# BG1094_RPi3b__Connector.net
KiCad netlist of a schematic drawn in Altium Designer
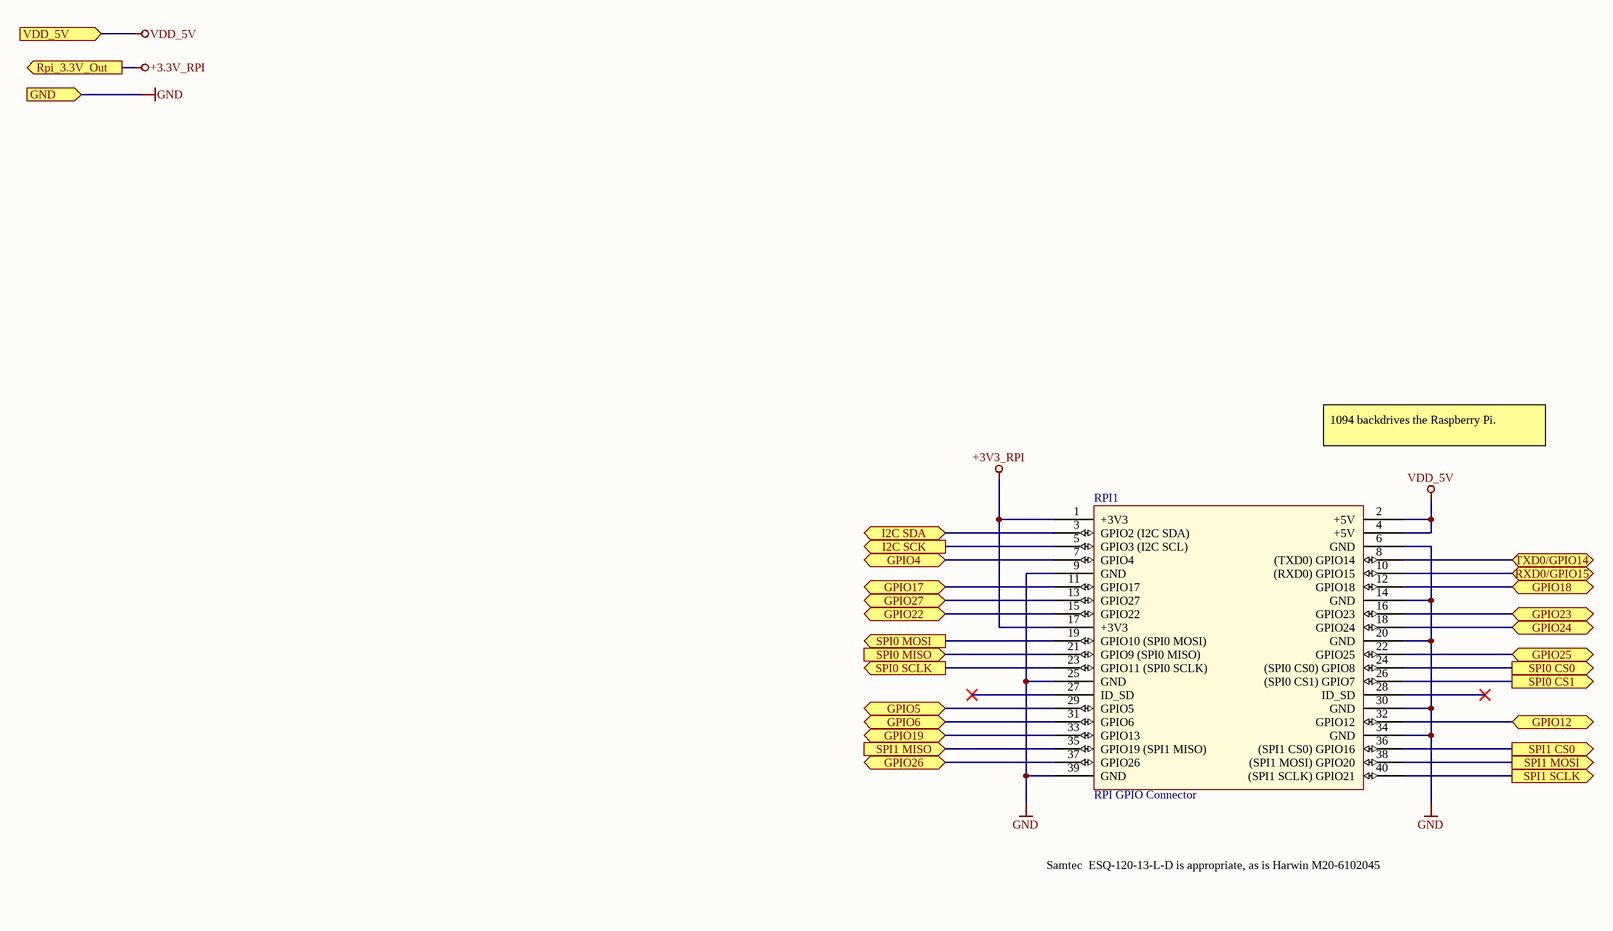
[diagram p0: BG1094_RPi3b+_Connector.SchDoc]

(export (version "E")
  (design (tool "Eeschema 10.0.6"))
  (components
    (comp (ref "RPI1")
      (value "RPI GPIO Connector")
      (footprint "Luxonis:rpi-hat-40-socket")
      (description "GPIO Header for Raspberry Pi A+/B+/Pi 2/Pi 3 - 2x20")
      (libsource (lib "Luxonis") (part "RPi HAT 40 Pin Connector"))
    )
  )
  (nets
    (net (code "2") (name "+3V3_RPI") (class "Default")
      (node (ref "RPI1") (pin "1") (pinfunction "+3V3_1") (pintype "power_in"))
      (node (ref "RPI1") (pin "17") (pinfunction "+3V3_17") (pintype "power_in"))
    )
    (net (code "3") (name "/GPIO4") (class "Default")
      (node (ref "RPI1") (pin "7") (pinfunction "GPIO4_7") (pintype "bidirectional"))
    )
    (net (code "4") (name "/GPIO5") (class "Default")
      (node (ref "RPI1") (pin "29") (pinfunction "GPIO5_29") (pintype "bidirectional"))
    )
    (net (code "5") (name "/GPIO6") (class "Default")
      (node (ref "RPI1") (pin "31") (pinfunction "GPIO6_31") (pintype "bidirectional"))
    )
    (net (code "6") (name "/GPIO12") (class "Default")
      (node (ref "RPI1") (pin "32") (pinfunction "GPIO12_32") (pintype "bidirectional"))
    )
    (net (code "7") (name "/GPIO17") (class "Default")
      (node (ref "RPI1") (pin "11") (pinfunction "GPIO17_11") (pintype "bidirectional"))
    )
    (net (code "8") (name "/GPIO18") (class "Default")
      (node (ref "RPI1") (pin "12") (pinfunction "GPIO18_12") (pintype "bidirectional"))
    )
    (net (code "9") (name "/GPIO19") (class "Default")
      (node (ref "RPI1") (pin "33") (pinfunction "GPIO13_33") (pintype "bidirectional"))
    )
    (net (code "10") (name "/GPIO22") (class "Default")
      (node (ref "RPI1") (pin "15") (pinfunction "GPIO22_15") (pintype "bidirectional"))
    )
    (net (code "11") (name "/GPIO23") (class "Default")
      (node (ref "RPI1") (pin "16") (pinfunction "GPIO23_16") (pintype "bidirectional"))
    )
    (net (code "12") (name "/GPIO24") (class "Default")
      (node (ref "RPI1") (pin "18") (pinfunction "GPIO24_18") (pintype "bidirectional"))
    )
    (net (code "13") (name "/GPIO25") (class "Default")
      (node (ref "RPI1") (pin "22") (pinfunction "GPIO25_22") (pintype "bidirectional"))
    )
    (net (code "14") (name "/GPIO26") (class "Default")
      (node (ref "RPI1") (pin "37") (pinfunction "GPIO26_37") (pintype "bidirectional"))
    )
    (net (code "15") (name "/GPIO27") (class "Default")
      (node (ref "RPI1") (pin "13") (pinfunction "GPIO27_13") (pintype "bidirectional"))
    )
    (net (code "16") (name "/I2C SCK") (class "Default")
      (node (ref "RPI1") (pin "5") (pinfunction "GPIO3_(I2C_SCL)_5") (pintype "bidirectional"))
    )
    (net (code "17") (name "/I2C SDA") (class "Default")
      (node (ref "RPI1") (pin "3") (pinfunction "GPIO2_(I2C_SDA)_3") (pintype "bidirectional"))
    )
    (net (code "18") (name "/RXD0{slash}GPIO15") (class "Default")
      (node (ref "RPI1") (pin "10") (pinfunction "(RXD0)_GPIO15_10") (pintype "bidirectional"))
    )
    (net (code "19") (name "/SPI0 CS0") (class "Default")
      (node (ref "RPI1") (pin "24") (pinfunction "(SPI0_CS0)_GPIO8_24") (pintype "bidirectional"))
    )
    (net (code "20") (name "/SPI0 CS1") (class "Default")
      (node (ref "RPI1") (pin "26") (pinfunction "(SPI0_CS1)_GPIO7_26") (pintype "bidirectional"))
    )
    (net (code "21") (name "/SPI0 MISO") (class "Default")
      (node (ref "RPI1") (pin "21") (pinfunction "GPIO9_(SPI0_MISO)_21") (pintype "bidirectional"))
    )
    (net (code "22") (name "/SPI0 MOSI") (class "Default")
      (node (ref "RPI1") (pin "19") (pinfunction "GPIO10_(SPI0_MOSI)_19") (pintype "bidirectional"))
    )
    (net (code "23") (name "/SPI0 SCLK") (class "Default")
      (node (ref "RPI1") (pin "23") (pinfunction "GPIO11_(SPI0_SCLK)_23") (pintype "bidirectional"))
    )
    (net (code "24") (name "/SPI1 CS0") (class "Default")
      (node (ref "RPI1") (pin "36") (pinfunction "(SPI1_CS0)_GPIO16_36") (pintype "bidirectional"))
    )
    (net (code "25") (name "/SPI1 MISO") (class "Default")
      (node (ref "RPI1") (pin "35") (pinfunction "GPIO19_(SPI1_MISO)_35") (pintype "bidirectional"))
    )
    (net (code "26") (name "/SPI1 MOSI") (class "Default")
      (node (ref "RPI1") (pin "38") (pinfunction "(SPI1_MOSI)_GPIO20_38") (pintype "bidirectional"))
    )
    (net (code "27") (name "/SPI1 SCLK") (class "Default")
      (node (ref "RPI1") (pin "40") (pinfunction "(SPI1_SCLK)_GPIO21_40") (pintype "bidirectional"))
    )
    (net (code "28") (name "/TXD0{slash}GPIO14") (class "Default")
      (node (ref "RPI1") (pin "8") (pinfunction "(TXD0)_GPIO14_8") (pintype "bidirectional"))
    )
    (net (code "29") (name "GND") (class "Default")
      (node (ref "RPI1") (pin "14") (pinfunction "GND_14") (pintype "passive"))
      (node (ref "RPI1") (pin "20") (pinfunction "GND_20") (pintype "passive"))
      (node (ref "RPI1") (pin "25") (pinfunction "GND_25") (pintype "passive"))
      (node (ref "RPI1") (pin "30") (pinfunction "GND_30") (pintype "passive"))
      (node (ref "RPI1") (pin "34") (pinfunction "GND_34") (pintype "passive"))
      (node (ref "RPI1") (pin "39") (pinfunction "GND_39") (pintype "passive"))
      (node (ref "RPI1") (pin "6") (pinfunction "GND_6") (pintype "passive"))
      (node (ref "RPI1") (pin "9") (pinfunction "GND_9") (pintype "passive"))
    )
    (net (code "30") (name "VDD_5V") (class "Default")
      (node (ref "RPI1") (pin "2") (pinfunction "+5V_2") (pintype "power_in"))
      (node (ref "RPI1") (pin "4") (pinfunction "+5V_4") (pintype "power_in"))
    )
    (net (code "31") (name "unconnected-(RPI1-ID_SD-Pad27)") (class "Default")
      (node (ref "RPI1") (pin "27") (pinfunction "ID_SD_27") (pintype "passive+no_connect"))
    )
    (net (code "32") (name "unconnected-(RPI1-ID_SD-Pad28)") (class "Default")
      (node (ref "RPI1") (pin "28") (pinfunction "ID_SD_28") (pintype "passive+no_connect"))
    )
  )
)
